# OC_PROT_with_5V.net
KiCad netlist of a schematic drawn in Altium Designer
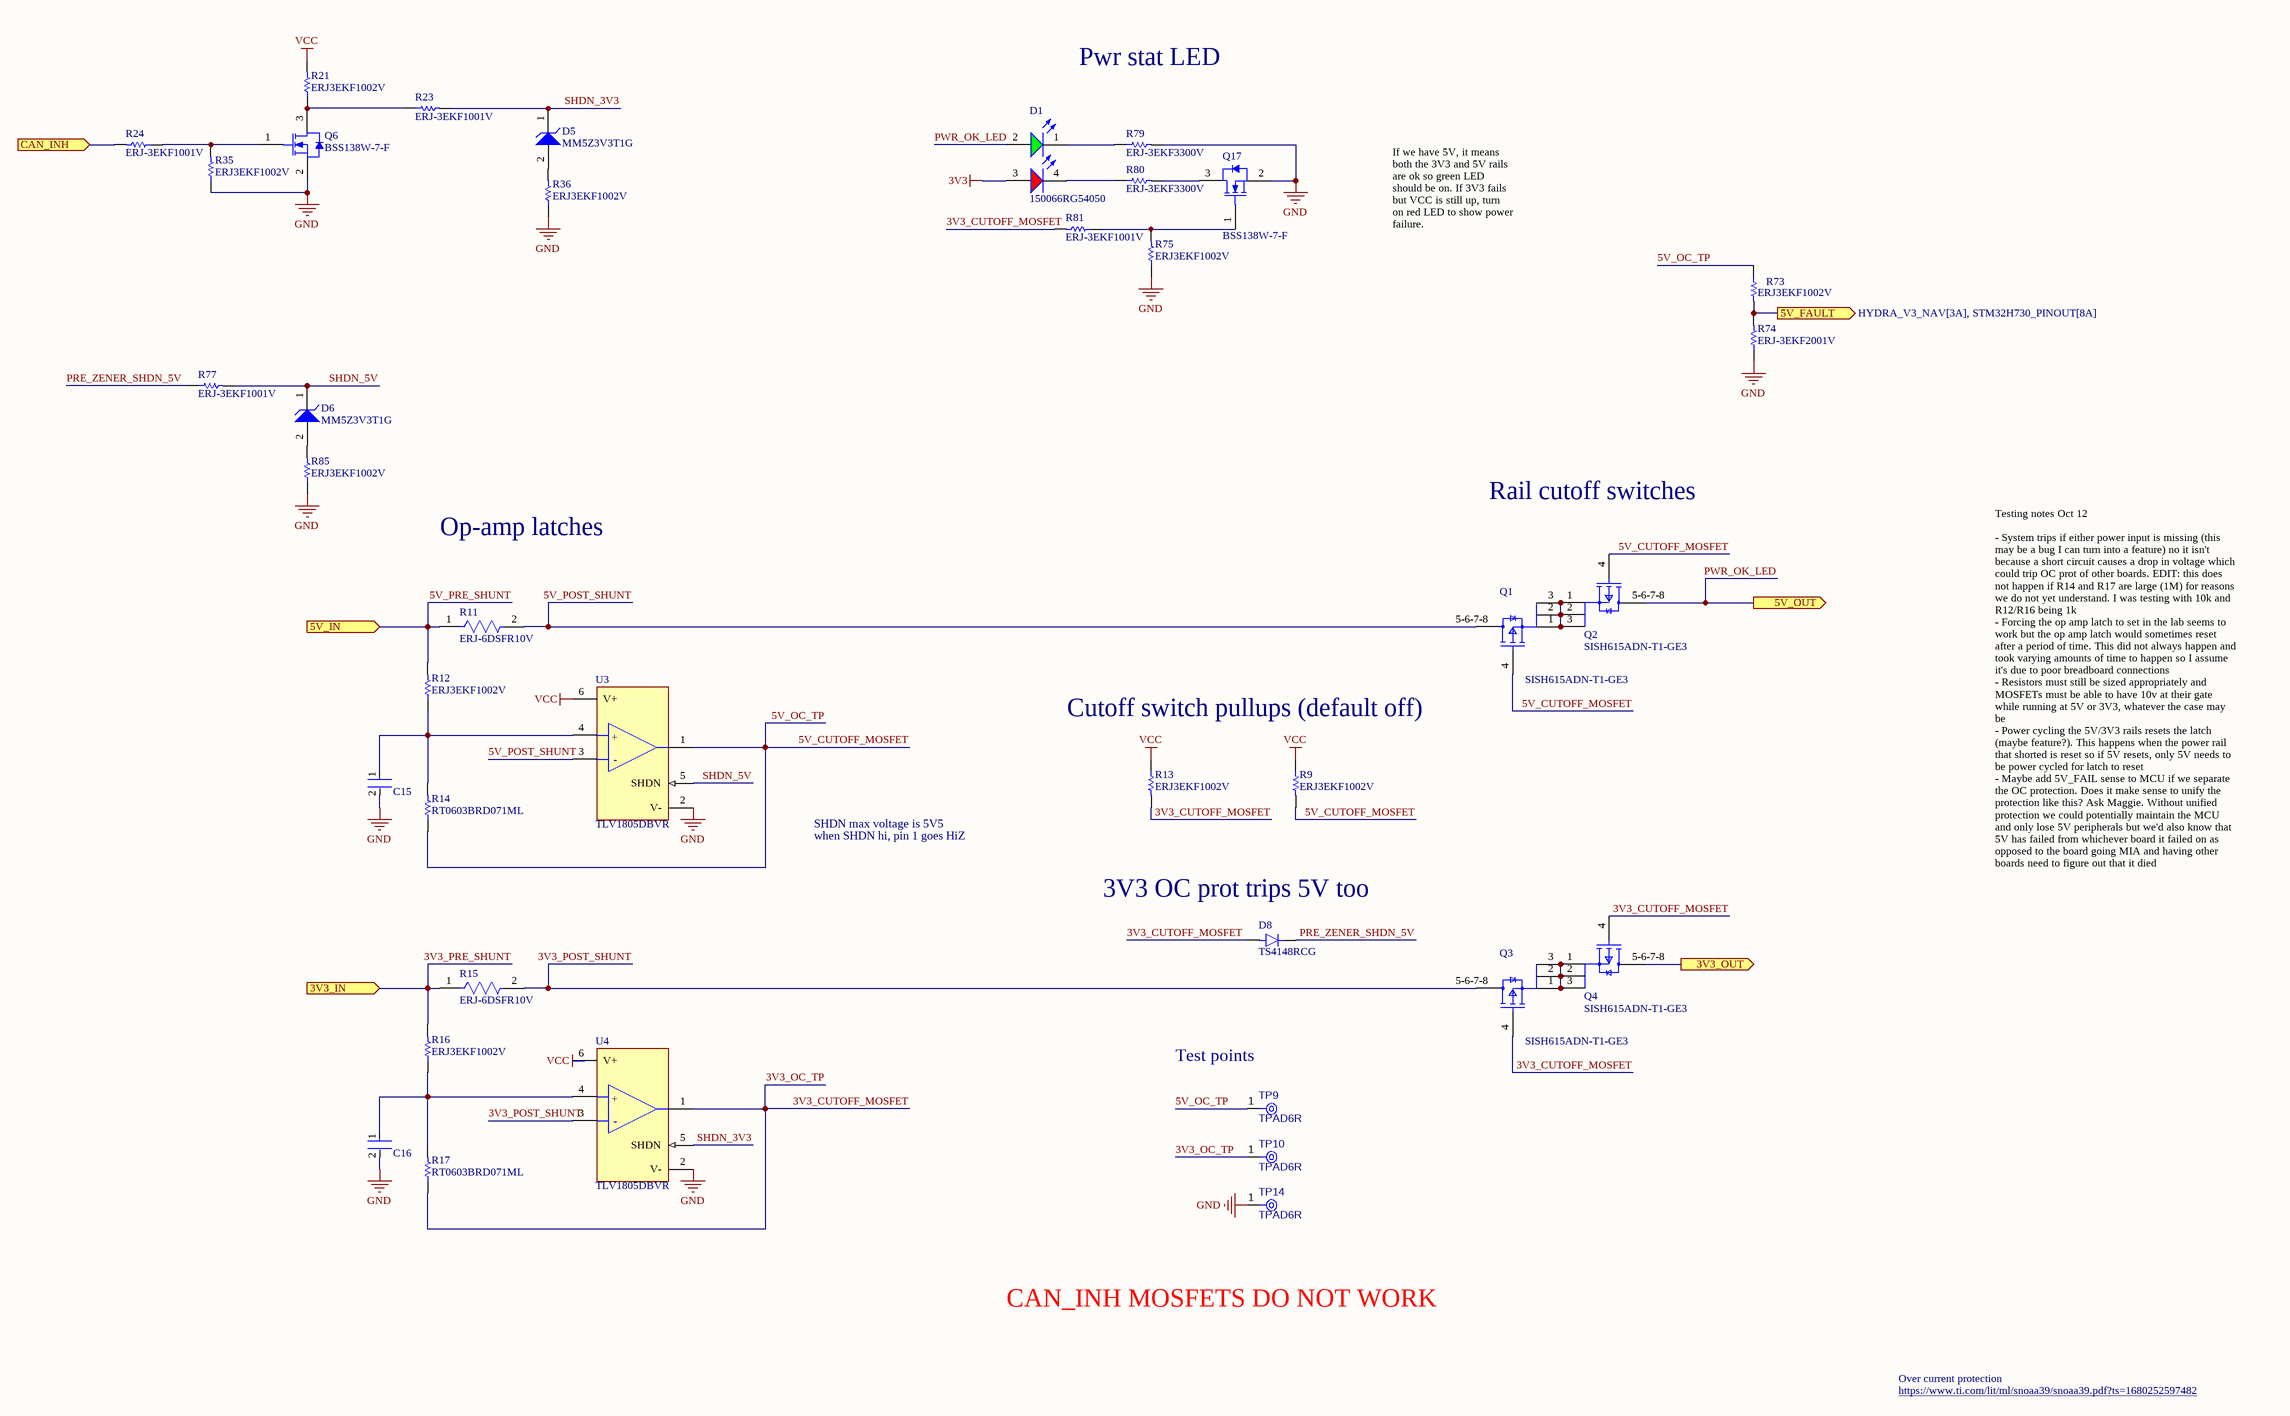
[diagram p0: OC_PROT_with_5V.SchDoc]

(export (version "E")
  (design (tool "Eeschema 10.0.6"))
  (components
    (comp (ref "C15")
      (value "C0402C104K8PACTU")
      (footprint "FP-C0402-BB-MFG")
      (description "CAP CER 0.1UF 10V X5R 0402")
      (fields (field (name "MANUFACTURER") "Kemet") (field (name "TOLERANCE") "0.1"))
      (libsource (lib "Altium Content Vault") (part "b4654b650e69147ec39a6b967a45e02"))
    )
    (comp (ref "C16")
      (value "C0402C104K8PACTU")
      (footprint "FP-C0402-BB-MFG")
      (description "CAP CER 0.1UF 10V X5R 0402")
      (fields (field (name "MANUFACTURER") "Kemet") (field (name "TOLERANCE") "0.1"))
      (libsource (lib "Altium Content Vault") (part "b4654b650e69147ec39a6b967a45e02"))
    )
    (comp (ref "D1")
      (value "150066RG54050")
      (footprint "WL-SBCD_0606")
      (description "Led, Red/Grn, 180Mcd/230Mcd, 624Nm/525Nm Rohs Compliant: Yes")
      (fields (field (name "SOURCE") "rgled.SchLib"))
      (libsource (lib "Space Concordia") (part "CMP-004-00034-2"))
    )
    (comp (ref "D5")
      (value "MM5Z3V3T1G")
      (footprint "ONSC-SOD-523-2-502-01_V")
      (description "Zener Voltage Regulator, 500 mW, 2-Pin SOD-523, Pb-Free, Tape and Reel")
      (fields (field (name "MANUFACTURER") "On Semiconductor"))
      (libsource (lib "Altium Content Vault") (part "ONSC-K1A2-2"))
    )
    (comp (ref "D6")
      (value "MM5Z3V3T1G")
      (footprint "ONSC-SOD-523-2-502-01_V")
      (description "Zener Voltage Regulator, 500 mW, 2-Pin SOD-523, Pb-Free, Tape and Reel")
      (fields (field (name "MANUFACTURER") "On Semiconductor"))
      (libsource (lib "Altium Content Vault") (part "ONSC-K1A2-2"))
    )
    (comp (ref "D8")
      (value "TS4148RCG")
      (footprint "TS4148RCG-Footprint-1")
      (description "SMD Si-Diode 75V 100mA 0603")
      (libsource (lib "uORocketry Hardware") (part "TS4148RCG"))
    )
    (comp (ref "Q1")
      (value "SISH615ADN-T1-GE3")
      (footprint "SISH615ADN-T1-GE3-Footprint-1")
      (description "Trans MOSFET P-CH 20V 22.1A 8-Pin PowerPAK 1212 EP T/R")
      (libsource (lib "uORocketry Hardware") (part "SISH615ADN-T1-GE3-Symbol-1"))
    )
    (comp (ref "Q2")
      (value "SISH615ADN-T1-GE3")
      (footprint "SISH615ADN-T1-GE3-Footprint-1")
      (description "Trans MOSFET P-CH 20V 22.1A 8-Pin PowerPAK 1212 EP T/R")
      (libsource (lib "uORocketry Hardware") (part "SISH615ADN-T1-GE3-Symbol-1"))
    )
    (comp (ref "Q3")
      (value "SISH615ADN-T1-GE3")
      (footprint "SISH615ADN-T1-GE3-Footprint-1")
      (description "Trans MOSFET P-CH 20V 22.1A 8-Pin PowerPAK 1212 EP T/R")
      (libsource (lib "uORocketry Hardware") (part "SISH615ADN-T1-GE3-Symbol-1"))
    )
    (comp (ref "Q4")
      (value "SISH615ADN-T1-GE3")
      (footprint "SISH615ADN-T1-GE3-Footprint-1")
      (description "Trans MOSFET P-CH 20V 22.1A 8-Pin PowerPAK 1212 EP T/R")
      (libsource (lib "uORocketry Hardware") (part "SISH615ADN-T1-GE3-Symbol-1"))
    )
    (comp (ref "Q6")
      (value "BSS138W-7-F")
      (footprint "DIOD-SOT323-3_V")
      (fields (field (name "MANUFACTURER") "DiodesIncorporated"))
      (libsource (lib "Altium Content Vault") (part "NEMOS-GSD-3"))
    )
    (comp (ref "Q17")
      (value "BSS138W-7-F")
      (footprint "DIOD-SOT323-3_V")
      (fields (field (name "MANUFACTURER") "DiodesIncorporated"))
      (libsource (lib "Altium Content Vault") (part "NEMOS-GSD-3"))
    )
    (comp (ref "R9")
      (value "ERJ3EKF1002V")
      (footprint "RESC1609X55X30LL15T15")
      (description "Chip Resistor, 10 KOhm, +/- 1%, 0.1 W, -55 to 155 degC, 0603 (1608 Metric), RoHS, Tape and Reel")
      (fields (field (name "TOLERANCE") "1%") (field (name "MANUFACTURER") "Panasonic"))
      (libsource (lib "Altium Content Vault") (part "RES-2"))
    )
    (comp (ref "R11")
      (value "ERJ-6DSFR10V")
      (footprint "FP-ERJ6D-MFG")
      (description "RES 0.1 OHM 1% 1/2W 0805")
      (fields (field (name "TOLERANCE") "1%"))
      (libsource (lib "Altium Content Vault") (part "1029c3af85768c4190bb7ad29bc67b5"))
    )
    (comp (ref "R12")
      (value "ERJ3EKF1002V")
      (footprint "RESC1609X55X30LL15T15")
      (description "Chip Resistor, 10 KOhm, +/- 1%, 0.1 W, -55 to 155 degC, 0603 (1608 Metric), RoHS, Tape and Reel")
      (fields (field (name "TOLERANCE") "1%") (field (name "MANUFACTURER") "Panasonic"))
      (libsource (lib "Altium Content Vault") (part "RES-2"))
    )
    (comp (ref "R13")
      (value "ERJ3EKF1002V")
      (footprint "RESC1609X55X30LL15T15")
      (description "Chip Resistor, 10 KOhm, +/- 1%, 0.1 W, -55 to 155 degC, 0603 (1608 Metric), RoHS, Tape and Reel")
      (fields (field (name "TOLERANCE") "1%") (field (name "MANUFACTURER") "Panasonic"))
      (libsource (lib "Altium Content Vault") (part "RES-2"))
    )
    (comp (ref "R14")
      (value "RT0603BRD071ML")
      (footprint "RESC1608X55X30NL20T20")
      (fields (field (name "MANUFACTURER") "Panasonic") (field (name "PART NUMBER") "ERA-3AEB163V"))
      (libsource (lib "Altium Content Vault") (part "RES"))
    )
    (comp (ref "R15")
      (value "ERJ-6DSFR10V")
      (footprint "FP-ERJ6D-MFG")
      (description "RES 0.1 OHM 1% 1/2W 0805")
      (fields (field (name "TOLERANCE") "1%"))
      (libsource (lib "Altium Content Vault") (part "1029c3af85768c4190bb7ad29bc67b5"))
    )
    (comp (ref "R16")
      (value "ERJ3EKF1002V")
      (footprint "RESC1609X55X30LL15T15")
      (description "Chip Resistor, 10 KOhm, +/- 1%, 0.1 W, -55 to 155 degC, 0603 (1608 Metric), RoHS, Tape and Reel")
      (fields (field (name "TOLERANCE") "1%") (field (name "MANUFACTURER") "Panasonic"))
      (libsource (lib "Altium Content Vault") (part "RES-2"))
    )
    (comp (ref "R17")
      (value "RT0603BRD071ML")
      (footprint "RESC1608X55X30NL20T20")
      (fields (field (name "MANUFACTURER") "Panasonic") (field (name "PART NUMBER") "ERA-3AEB163V"))
      (libsource (lib "Altium Content Vault") (part "RES"))
    )
    (comp (ref "R21")
      (value "ERJ3EKF1002V")
      (footprint "RESC1609X55X30LL15T15")
      (description "Chip Resistor, 10 KOhm, +/- 1%, 0.1 W, -55 to 155 degC, 0603 (1608 Metric), RoHS, Tape and Reel")
      (fields (field (name "TOLERANCE") "1%") (field (name "MANUFACTURER") "Panasonic"))
      (libsource (lib "Altium Content Vault") (part "RES-2"))
    )
    (comp (ref "R23")
      (value "ERJ-3EKF1001V")
      (footprint "RESC1608X55X30LL15T15")
      (fields (field (name "MANUFACTURER") "Panasonic"))
      (libsource (lib "Altium Content Vault") (part "RES"))
    )
    (comp (ref "R24")
      (value "ERJ-3EKF1001V")
      (footprint "RESC1608X55X30LL15T15")
      (fields (field (name "MANUFACTURER") "Panasonic"))
      (libsource (lib "Altium Content Vault") (part "RES"))
    )
    (comp (ref "R35")
      (value "ERJ3EKF1002V")
      (footprint "RESC1609X55X30LL15T15")
      (description "Chip Resistor, 10 KOhm, +/- 1%, 0.1 W, -55 to 155 degC, 0603 (1608 Metric), RoHS, Tape and Reel")
      (fields (field (name "TOLERANCE") "1%") (field (name "MANUFACTURER") "Panasonic"))
      (libsource (lib "Altium Content Vault") (part "RES-2"))
    )
    (comp (ref "R36")
      (value "ERJ3EKF1002V")
      (footprint "RESC1609X55X30LL15T15")
      (description "Chip Resistor, 10 KOhm, +/- 1%, 0.1 W, -55 to 155 degC, 0603 (1608 Metric), RoHS, Tape and Reel")
      (fields (field (name "TOLERANCE") "1%") (field (name "MANUFACTURER") "Panasonic"))
      (libsource (lib "Altium Content Vault") (part "RES-2"))
    )
    (comp (ref "R73")
      (value "ERJ3EKF1002V")
      (footprint "RESC1609X55X30LL15T15")
      (description "Chip Resistor, 10 KOhm, +/- 1%, 0.1 W, -55 to 155 degC, 0603 (1608 Metric), RoHS, Tape and Reel")
      (fields (field (name "TOLERANCE") "1%") (field (name "MANUFACTURER") "Panasonic"))
      (libsource (lib "Altium Content Vault") (part "RES-2"))
    )
    (comp (ref "R74")
      (value "ERJ-3EKF2001V")
      (footprint "RESC1608X55X30ML15T15")
      (fields (field (name "MANUFACTURER") "Panasonic"))
      (libsource (lib "Altium Content Vault") (part "RES"))
    )
    (comp (ref "R75")
      (value "ERJ3EKF1002V")
      (footprint "RESC1609X55X30LL15T15")
      (description "Chip Resistor, 10 KOhm, +/- 1%, 0.1 W, -55 to 155 degC, 0603 (1608 Metric), RoHS, Tape and Reel")
      (fields (field (name "TOLERANCE") "1%") (field (name "MANUFACTURER") "Panasonic"))
      (libsource (lib "Altium Content Vault") (part "RES-2"))
    )
    (comp (ref "R77")
      (value "ERJ-3EKF1001V")
      (footprint "RESC1608X55X30LL15T15")
      (fields (field (name "MANUFACTURER") "Panasonic"))
      (libsource (lib "Altium Content Vault") (part "RES"))
    )
    (comp (ref "R79")
      (value "ERJ-3EKF3300V")
      (footprint "RESC1608X55X30LL15T15")
      (description "Chip Resistor, 330 Ohm, +/- 1%, 0.1 W, -55 to 155 degC, 0603 (1608 Metric), RoHS, Tape and Reel")
      (libsource (lib "Altium Content Vault") (part "RES-2"))
    )
    (comp (ref "R80")
      (value "ERJ-3EKF3300V")
      (footprint "RESC1608X55X30LL15T15")
      (description "Chip Resistor, 330 Ohm, +/- 1%, 0.1 W, -55 to 155 degC, 0603 (1608 Metric), RoHS, Tape and Reel")
      (libsource (lib "Altium Content Vault") (part "RES-2"))
    )
    (comp (ref "R81")
      (value "ERJ-3EKF1001V")
      (footprint "RESC1608X55X30LL15T15")
      (fields (field (name "MANUFACTURER") "Panasonic"))
      (libsource (lib "Altium Content Vault") (part "RES"))
    )
    (comp (ref "R85")
      (value "ERJ3EKF1002V")
      (footprint "RESC1609X55X30LL15T15")
      (description "Chip Resistor, 10 KOhm, +/- 1%, 0.1 W, -55 to 155 degC, 0603 (1608 Metric), RoHS, Tape and Reel")
      (fields (field (name "TOLERANCE") "1%") (field (name "MANUFACTURER") "Panasonic"))
      (libsource (lib "Altium Content Vault") (part "RES-2"))
    )
    (comp (ref "TP9")
      (value "TPAD6R")
      (footprint "TP06R")
      (description "0.6mm round")
      (libsource (lib "uORocketry Hardware") (part "CMP-001-0001-4"))
    )
    (comp (ref "TP10")
      (value "TPAD6R")
      (footprint "TP06R")
      (description "0.6mm round")
      (libsource (lib "uORocketry Hardware") (part "CMP-001-0001-4"))
    )
    (comp (ref "TP14")
      (value "TPAD6R")
      (footprint "TP06R")
      (description "0.6mm round")
      (libsource (lib "uORocketry Hardware") (part "CMP-001-0001-4"))
    )
    (comp (ref "U3")
      (value "TLV1805DBVR")
      (footprint "FP-DBV0006A-IPC_C")
      (description "40V, RAIL-TO-RAIL INPUT, PUSH-PU")
      (libsource (lib "Altium Content Vault") (part "c7aa3bc3dbf0dc8b0b0354779bd1228"))
    )
    (comp (ref "U4")
      (value "TLV1805DBVR")
      (footprint "FP-DBV0006A-IPC_C")
      (description "40V, RAIL-TO-RAIL INPUT, PUSH-PU")
      (libsource (lib "Altium Content Vault") (part "c7aa3bc3dbf0dc8b0b0354779bd1228"))
    )
  )
  (nets
    (net (code "1") (name "/3V3_CUTOFF_MOSFET") (class "Default")
      (node (ref "D8") (pin "A") (pinfunction "A_A") (pintype "passive"))
      (node (ref "Q3") (pin "4") (pinfunction "G_4") (pintype "passive"))
      (node (ref "Q4") (pin "4") (pinfunction "G_4") (pintype "passive"))
      (node (ref "R13") (pin "2") (pinfunction "2_2") (pintype "passive"))
      (node (ref "R17") (pin "1") (pinfunction "1_1") (pintype "passive"))
      (node (ref "R81") (pin "2") (pinfunction "2_2") (pintype "passive"))
      (node (ref "TP10") (pin "1") (pinfunction "TP_1") (pintype "passive"))
      (node (ref "U4") (pin "1") (pinfunction "OUT_1") (pintype "passive"))
    )
    (net (code "2") (name "/3V3_OUT") (class "Default")
      (node (ref "Q4") (pin "5-6-7-8") (pinfunction "D_5-6-7-8") (pintype "passive"))
    )
    (net (code "3") (name "/3V3_POST_SHUNT") (class "Default")
      (node (ref "Q3") (pin "5-6-7-8") (pinfunction "D_5-6-7-8") (pintype "passive"))
      (node (ref "R15") (pin "2") (pinfunction "2_2") (pintype "passive"))
      (node (ref "U4") (pin "3") (pinfunction "-IN_3") (pintype "tri_state"))
    )
    (net (code "4") (name "/3V3_PRE_SHUNT") (class "Default")
      (node (ref "R15") (pin "1") (pinfunction "1_1") (pintype "passive"))
      (node (ref "R16") (pin "2") (pinfunction "2_2") (pintype "passive"))
    )
    (net (code "5") (name "/5V_CUTOFF_MOSFET") (class "Default")
      (node (ref "Q1") (pin "4") (pinfunction "G_4") (pintype "passive"))
      (node (ref "Q2") (pin "4") (pinfunction "G_4") (pintype "passive"))
      (node (ref "R14") (pin "1") (pinfunction "1_1") (pintype "passive"))
      (node (ref "R73") (pin "1") (pinfunction "1_1") (pintype "passive"))
      (node (ref "R9") (pin "2") (pinfunction "2_2") (pintype "passive"))
      (node (ref "TP9") (pin "1") (pinfunction "TP_1") (pintype "passive"))
      (node (ref "U3") (pin "1") (pinfunction "OUT_1") (pintype "passive"))
    )
    (net (code "6") (name "/5V_FAULT") (class "Default")
      (node (ref "R73") (pin "2") (pinfunction "2_2") (pintype "passive"))
      (node (ref "R74") (pin "2") (pinfunction "2_2") (pintype "passive"))
    )
    (net (code "7") (name "/5V_POST_SHUNT") (class "Default")
      (node (ref "Q1") (pin "5-6-7-8") (pinfunction "D_5-6-7-8") (pintype "passive"))
      (node (ref "R11") (pin "2") (pinfunction "2_2") (pintype "passive"))
      (node (ref "U3") (pin "3") (pinfunction "-IN_3") (pintype "tri_state"))
    )
    (net (code "8") (name "/5V_PRE_SHUNT") (class "Default")
      (node (ref "R11") (pin "1") (pinfunction "1_1") (pintype "passive"))
      (node (ref "R12") (pin "2") (pinfunction "2_2") (pintype "passive"))
    )
    (net (code "9") (name "/CAN_INH") (class "Default")
      (node (ref "R24") (pin "2") (pinfunction "2_2") (pintype "passive"))
    )
    (net (code "10") (name "/PRE_ZENER_SHDN_5V") (class "Default")
      (node (ref "D8") (pin "C") (pinfunction "K_C") (pintype "passive"))
      (node (ref "R77") (pin "1") (pinfunction "1_1") (pintype "passive"))
    )
    (net (code "11") (name "/PWR_OK_LED") (class "Default")
      (node (ref "D1") (pin "2") (pinfunction "A_2") (pintype "passive"))
      (node (ref "Q2") (pin "5-6-7-8") (pinfunction "D_5-6-7-8") (pintype "passive"))
    )
    (net (code "12") (name "/SHDN_3V3") (class "Default")
      (node (ref "D5") (pin "1") (pinfunction "K_1") (pintype "passive"))
      (node (ref "R23") (pin "2") (pinfunction "2_2") (pintype "passive"))
      (node (ref "U4") (pin "5") (pinfunction "SHDN_5") (pintype "input"))
    )
    (net (code "13") (name "/SHDN_5V") (class "Default")
      (node (ref "D6") (pin "1") (pinfunction "K_1") (pintype "passive"))
      (node (ref "R77") (pin "2") (pinfunction "2_2") (pintype "passive"))
      (node (ref "U3") (pin "5") (pinfunction "SHDN_5") (pintype "input"))
    )
    (net (code "14") (name "3V3") (class "Default")
      (node (ref "D1") (pin "3") (pinfunction "A_3") (pintype "passive"))
    )
    (net (code "15") (name "GND") (class "Default")
      (node (ref "C15") (pin "2") (pinfunction "2_2") (pintype "passive"))
      (node (ref "C16") (pin "2") (pinfunction "2_2") (pintype "passive"))
      (node (ref "Q17") (pin "2") (pinfunction "S_2") (pintype "passive"))
      (node (ref "Q6") (pin "2") (pinfunction "S_2") (pintype "passive"))
      (node (ref "R35") (pin "1") (pinfunction "1_1") (pintype "passive"))
      (node (ref "R36") (pin "1") (pinfunction "1_1") (pintype "passive"))
      (node (ref "R74") (pin "1") (pinfunction "1_1") (pintype "passive"))
      (node (ref "R75") (pin "1") (pinfunction "1_1") (pintype "passive"))
      (node (ref "R79") (pin "2") (pinfunction "2_2") (pintype "passive"))
      (node (ref "R85") (pin "1") (pinfunction "1_1") (pintype "passive"))
      (node (ref "TP14") (pin "1") (pinfunction "TP_1") (pintype "passive"))
      (node (ref "U3") (pin "2") (pinfunction "V-_2") (pintype "power_in"))
      (node (ref "U4") (pin "2") (pinfunction "V-_2") (pintype "power_in"))
    )
    (net (code "16") (name "Net-(D1-K-Pad1)") (class "Default")
      (node (ref "D1") (pin "1") (pinfunction "K_1") (pintype "passive"))
      (node (ref "R79") (pin "1") (pinfunction "1_1") (pintype "passive"))
    )
    (net (code "17") (name "Net-(D1-K-Pad4)") (class "Default")
      (node (ref "D1") (pin "4") (pinfunction "K_4") (pintype "passive"))
      (node (ref "R80") (pin "1") (pinfunction "1_1") (pintype "passive"))
    )
    (net (code "18") (name "Net-(D5-A)") (class "Default")
      (node (ref "D5") (pin "2") (pinfunction "A_2") (pintype "passive"))
      (node (ref "R36") (pin "2") (pinfunction "2_2") (pintype "passive"))
    )
    (net (code "19") (name "Net-(D6-A)") (class "Default")
      (node (ref "D6") (pin "2") (pinfunction "A_2") (pintype "passive"))
      (node (ref "R85") (pin "2") (pinfunction "2_2") (pintype "passive"))
    )
    (net (code "20") (name "Net-(Q1-S-Pad1)") (class "Default")
      (node (ref "Q1") (pin "1") (pinfunction "S_1") (pintype "passive"))
      (node (ref "Q1") (pin "2") (pinfunction "S_2") (pintype "passive"))
      (node (ref "Q1") (pin "3") (pinfunction "S_3") (pintype "passive"))
      (node (ref "Q2") (pin "1") (pinfunction "S_1") (pintype "passive"))
      (node (ref "Q2") (pin "2") (pinfunction "S_2") (pintype "passive"))
      (node (ref "Q2") (pin "3") (pinfunction "S_3") (pintype "passive"))
    )
    (net (code "21") (name "Net-(Q3-S-Pad1)") (class "Default")
      (node (ref "Q3") (pin "1") (pinfunction "S_1") (pintype "passive"))
      (node (ref "Q3") (pin "2") (pinfunction "S_2") (pintype "passive"))
      (node (ref "Q3") (pin "3") (pinfunction "S_3") (pintype "passive"))
      (node (ref "Q4") (pin "1") (pinfunction "S_1") (pintype "passive"))
      (node (ref "Q4") (pin "2") (pinfunction "S_2") (pintype "passive"))
      (node (ref "Q4") (pin "3") (pinfunction "S_3") (pintype "passive"))
    )
    (net (code "22") (name "Net-(Q6-D)") (class "Default")
      (node (ref "Q6") (pin "3") (pinfunction "D_3") (pintype "passive"))
      (node (ref "R21") (pin "1") (pinfunction "1_1") (pintype "passive"))
      (node (ref "R23") (pin "1") (pinfunction "1_1") (pintype "passive"))
    )
    (net (code "23") (name "Net-(Q6-G)") (class "Default")
      (node (ref "Q6") (pin "1") (pinfunction "G_1") (pintype "passive"))
      (node (ref "R24") (pin "1") (pinfunction "1_1") (pintype "passive"))
      (node (ref "R35") (pin "2") (pinfunction "2_2") (pintype "passive"))
    )
    (net (code "24") (name "Net-(Q17-D)") (class "Default")
      (node (ref "Q17") (pin "3") (pinfunction "D_3") (pintype "passive"))
      (node (ref "R80") (pin "2") (pinfunction "2_2") (pintype "passive"))
    )
    (net (code "25") (name "Net-(Q17-G)") (class "Default")
      (node (ref "Q17") (pin "1") (pinfunction "G_1") (pintype "passive"))
      (node (ref "R75") (pin "2") (pinfunction "2_2") (pintype "passive"))
      (node (ref "R81") (pin "1") (pinfunction "1_1") (pintype "passive"))
    )
    (net (code "26") (name "Net-(U3-+IN)") (class "Default")
      (node (ref "C15") (pin "1") (pinfunction "1_1") (pintype "passive"))
      (node (ref "R12") (pin "1") (pinfunction "1_1") (pintype "passive"))
      (node (ref "R14") (pin "2") (pinfunction "2_2") (pintype "passive"))
      (node (ref "U3") (pin "4") (pinfunction "+IN_4") (pintype "tri_state"))
    )
    (net (code "27") (name "Net-(U4-+IN)") (class "Default")
      (node (ref "C16") (pin "1") (pinfunction "1_1") (pintype "passive"))
      (node (ref "R16") (pin "1") (pinfunction "1_1") (pintype "passive"))
      (node (ref "R17") (pin "2") (pinfunction "2_2") (pintype "passive"))
      (node (ref "U4") (pin "4") (pinfunction "+IN_4") (pintype "tri_state"))
    )
    (net (code "28") (name "VCC") (class "Default")
      (node (ref "R13") (pin "1") (pinfunction "1_1") (pintype "passive"))
      (node (ref "R21") (pin "2") (pinfunction "2_2") (pintype "passive"))
      (node (ref "R9") (pin "1") (pinfunction "1_1") (pintype "passive"))
      (node (ref "U3") (pin "6") (pinfunction "V+_6") (pintype "power_in"))
      (node (ref "U4") (pin "6") (pinfunction "V+_6") (pintype "power_in"))
    )
  )
)
